# SparkFun_Clock_Generator_5PV49V60.net
KiCad netlist of a schematic drawn in EAGLE
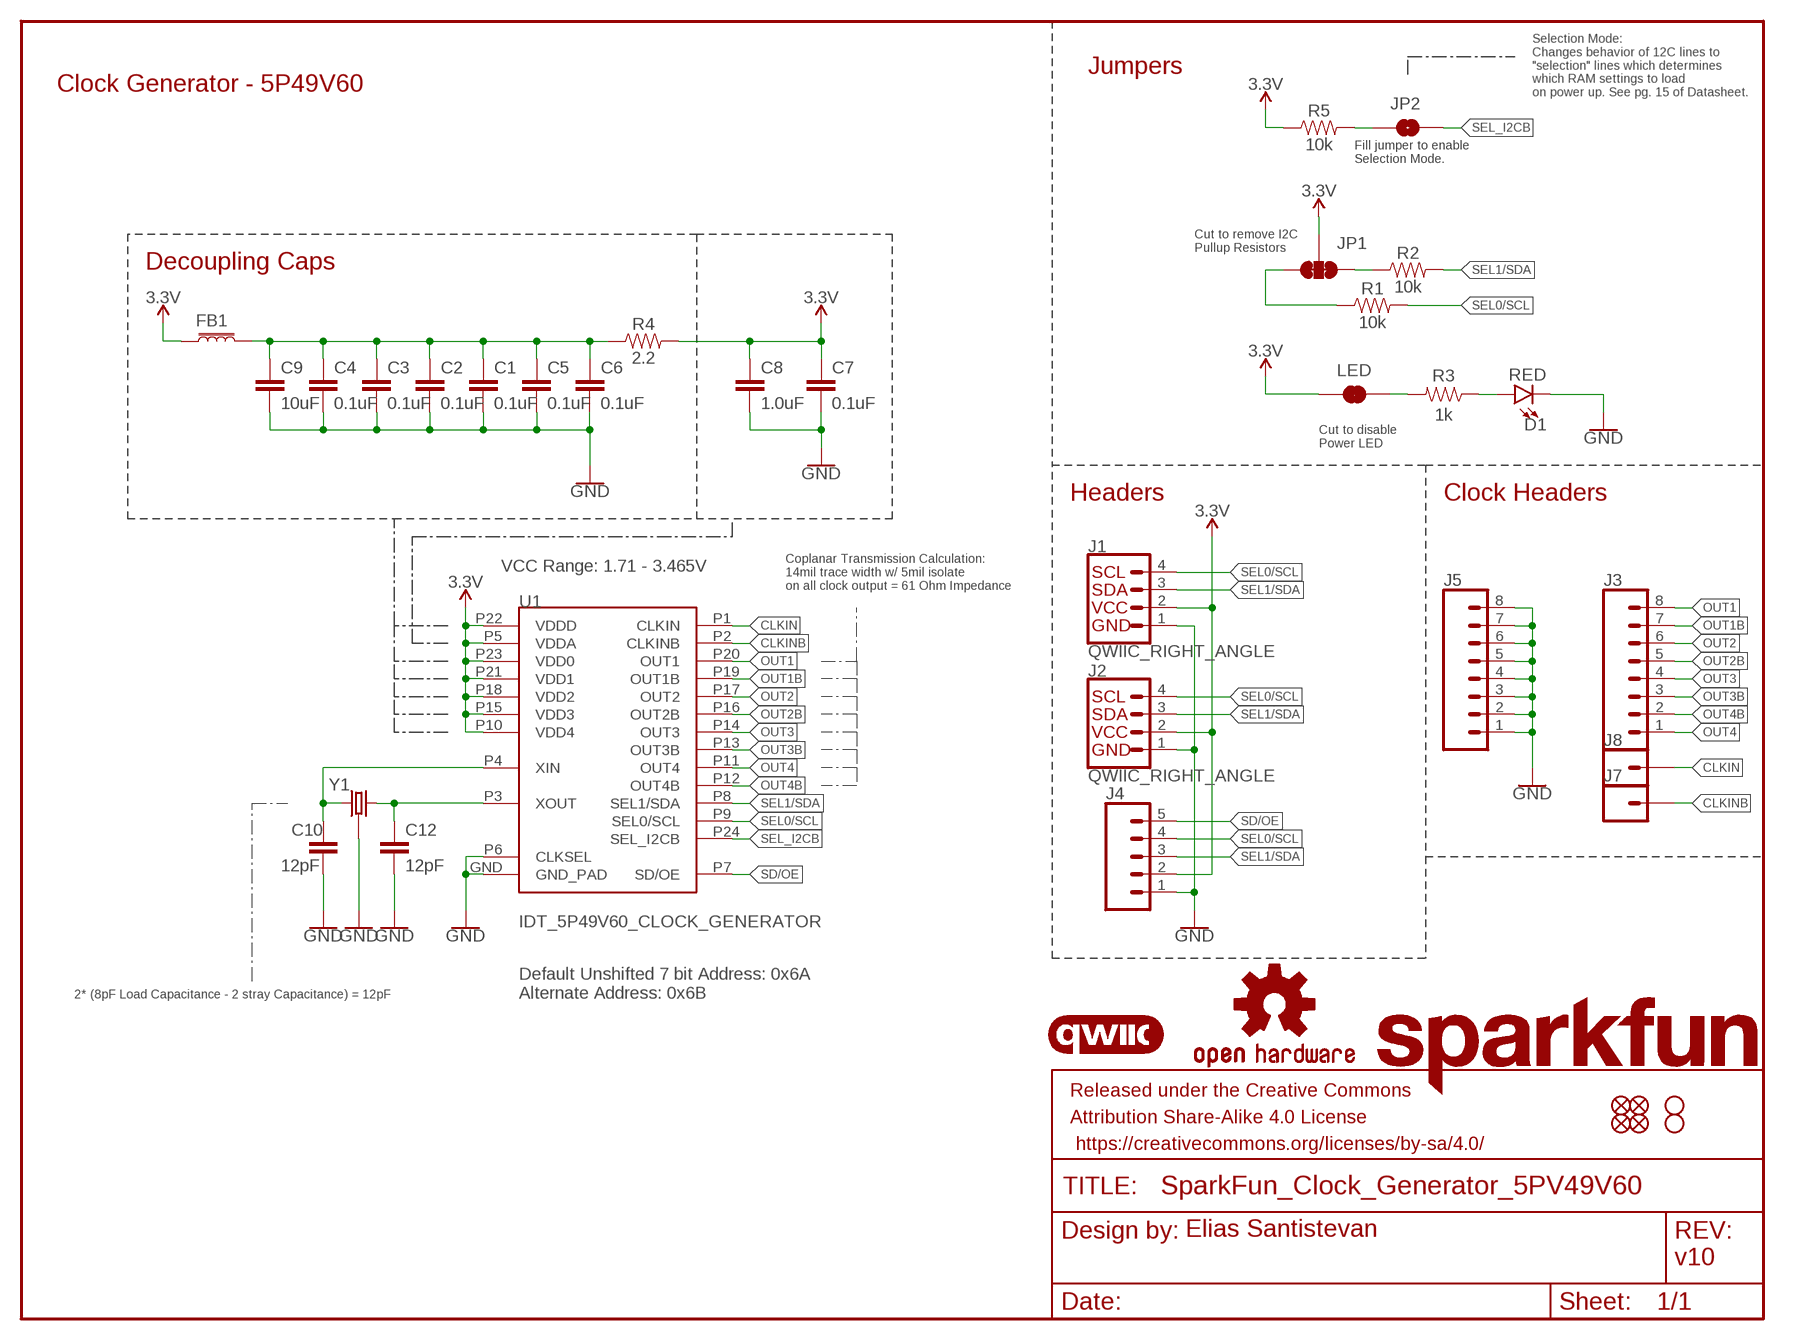
[diagram p0: schematic, sheet 1]

(export (version "E")
  (design (tool "Eeschema 10.0.6"))
  (components
    (comp (ref "C1")
      (value "0.1uF")
      (footprint "eagle-import:0402")
      (libsource (lib "eagle-import") (part "0.1UF-0402-16V-10%"))
    )
    (comp (ref "C2")
      (value "0.1uF")
      (footprint "eagle-import:0402")
      (libsource (lib "eagle-import") (part "0.1UF-0402-16V-10%"))
    )
    (comp (ref "C3")
      (value "0.1uF")
      (footprint "eagle-import:0402")
      (libsource (lib "eagle-import") (part "0.1UF-0402-16V-10%"))
    )
    (comp (ref "C4")
      (value "0.1uF")
      (footprint "eagle-import:0402")
      (libsource (lib "eagle-import") (part "0.1UF-0402-16V-10%"))
    )
    (comp (ref "C5")
      (value "0.1uF")
      (footprint "eagle-import:0402")
      (libsource (lib "eagle-import") (part "0.1UF-0402-16V-10%"))
    )
    (comp (ref "C6")
      (value "0.1uF")
      (footprint "eagle-import:0402")
      (libsource (lib "eagle-import") (part "0.1UF-0402-16V-10%"))
    )
    (comp (ref "C7")
      (value "0.1uF")
      (footprint "eagle-import:0402")
      (libsource (lib "eagle-import") (part "0.1UF-0402-16V-10%"))
    )
    (comp (ref "C8")
      (value "1.0uF")
      (footprint "eagle-import:0402")
      (libsource (lib "eagle-import") (part "1.0UF-0402-16V-10%"))
    )
    (comp (ref "C9")
      (value "10uF")
      (footprint "eagle-import:0603")
      (libsource (lib "eagle-import") (part "10UF-0603-6.3V-20%"))
    )
    (comp (ref "C10")
      (value "12pF")
      (footprint "eagle-import:0402")
      (libsource (lib "eagle-import") (part "12PF-0402-50V-5%"))
    )
    (comp (ref "C12")
      (value "12pF")
      (footprint "eagle-import:0402")
      (libsource (lib "eagle-import") (part "12PF-0402-50V-5%"))
    )
    (comp (ref "D1")
      (value "RED")
      (footprint "eagle-import:LED-0603")
      (libsource (lib "eagle-import") (part "LED-RED0603"))
    )
    (comp (ref "FB1")
      (value "FERRITE_BEAD-120_OHM-0402")
      (footprint "eagle-import:0402")
      (fields (field (name "MFG_PART") "BLM15HB121SN1D"))
      (libsource (lib "eagle-import") (part "FERRITE_BEAD-120_OHM-0402"))
    )
    (comp (ref "FD1")
      (value "FIDUCIALUFIDUCIAL")
      (footprint "eagle-import:FIDUCIAL-MICRO")
      (libsource (lib "eagle-import") (part "FIDUCIALUFIDUCIAL"))
    )
    (comp (ref "FD2")
      (value "FIDUCIALUFIDUCIAL")
      (footprint "eagle-import:FIDUCIAL-MICRO")
      (libsource (lib "eagle-import") (part "FIDUCIALUFIDUCIAL"))
    )
    (comp (ref "FD3")
      (value "FIDUCIALUFIDUCIAL")
      (footprint "eagle-import:FIDUCIAL-MICRO")
      (libsource (lib "eagle-import") (part "FIDUCIALUFIDUCIAL"))
    )
    (comp (ref "FD4")
      (value "FIDUCIALUFIDUCIAL")
      (footprint "eagle-import:FIDUCIAL-MICRO")
      (libsource (lib "eagle-import") (part "FIDUCIALUFIDUCIAL"))
    )
    (comp (ref "FRAME1")
      (value "FRAME-LETTER")
      (footprint "eagle-import:CREATIVE_COMMONS")
      (libsource (lib "eagle-import") (part "FRAME-LETTER"))
    )
    (comp (ref "H1")
      (value "STAND-OFFTIGHT")
      (footprint "eagle-import:STAND-OFF-TIGHT")
      (libsource (lib "eagle-import") (part "STAND-OFFTIGHT"))
    )
    (comp (ref "H2")
      (value "STAND-OFFTIGHT")
      (footprint "eagle-import:STAND-OFF-TIGHT")
      (libsource (lib "eagle-import") (part "STAND-OFFTIGHT"))
    )
    (comp (ref "J1")
      (value "QWIIC_RIGHT_ANGLE")
      (footprint "eagle-import:JST04_1MM_RA")
      (libsource (lib "eagle-import") (part "QWIIC_CONNECTORJS-1MM"))
    )
    (comp (ref "J2")
      (value "QWIIC_RIGHT_ANGLE")
      (footprint "eagle-import:JST04_1MM_RA")
      (libsource (lib "eagle-import") (part "QWIIC_CONNECTORJS-1MM"))
    )
    (comp (ref "J3")
      (value "CONN_08NO_SILK_FEMALE_PTH")
      (footprint "eagle-import:1X08_NO_SILK")
      (libsource (lib "eagle-import") (part "CONN_08NO_SILK_FEMALE_PTH"))
    )
    (comp (ref "J4")
      (value "CONN_05NO_SILK")
      (footprint "eagle-import:1X05_NO_SILK")
      (libsource (lib "eagle-import") (part "CONN_05NO_SILK"))
    )
    (comp (ref "J5")
      (value "CONN_08NO_SILK_FEMALE_PTH")
      (footprint "eagle-import:1X08_NO_SILK")
      (libsource (lib "eagle-import") (part "CONN_08NO_SILK_FEMALE_PTH"))
    )
    (comp (ref "J7")
      (value "CONN_01PTH_NO_SILK_SMALL")
      (footprint "eagle-import:1X01_SMALL")
      (libsource (lib "eagle-import") (part "CONN_01PTH_NO_SILK_SMALL"))
    )
    (comp (ref "J8")
      (value "CONN_01PTH_NO_SILK_SMALL")
      (footprint "eagle-import:1X01_SMALL")
      (libsource (lib "eagle-import") (part "CONN_01PTH_NO_SILK_SMALL"))
    )
    (comp (ref "JP1")
      (value "JUMPER-SMT_3_2-NC_TRACE_SILK")
      (footprint "eagle-import:SMT-JUMPER_3_2-NC_TRACE_SILK")
      (libsource (lib "eagle-import") (part "JUMPER-SMT_3_2-NC_TRACE_SILK"))
    )
    (comp (ref "JP2")
      (value "JUMPER-SMT_2_NO_SILK")
      (footprint "eagle-import:SMT-JUMPER_2_NO_SILK")
      (libsource (lib "eagle-import") (part "JUMPER-SMT_2_NO_SILK"))
    )
    (comp (ref "LED")
      (value "JUMPER-SMT_2_NC_TRACE_SILK")
      (footprint "eagle-import:SMT-JUMPER_2_NC_TRACE_SILK")
      (libsource (lib "eagle-import") (part "JUMPER-SMT_2_NC_TRACE_SILK"))
    )
    (comp (ref "LOGO1")
      (value "SFE_LOGO_NAME.1_INCH")
      (footprint "eagle-import:SFE_LOGO_NAME_.1")
      (libsource (lib "eagle-import") (part "SFE_LOGO_NAME.1_INCH"))
    )
    (comp (ref "LOGO2")
      (value "OSHW-LOGOS")
      (footprint "eagle-import:OSHW-LOGO-S")
      (libsource (lib "eagle-import") (part "OSHW-LOGOS"))
    )
    (comp (ref "LOGO3")
      (value "QWIIC_LOGO_4MM")
      (footprint "eagle-import:QWIIC_4MM")
      (libsource (lib "eagle-import") (part "QWIIC_LOGO_4MM"))
    )
    (comp (ref "R1")
      (value "10k")
      (footprint "eagle-import:0402")
      (libsource (lib "eagle-import") (part "10KOHM-0402-1/16W-1%"))
    )
    (comp (ref "R2")
      (value "10k")
      (footprint "eagle-import:0402")
      (libsource (lib "eagle-import") (part "10KOHM-0402-1/16W-1%"))
    )
    (comp (ref "R3")
      (value "1KOHM-0402-1/16W-1%")
      (footprint "eagle-import:0402")
      (libsource (lib "eagle-import") (part "1KOHM-0402-1/16W-1%"))
    )
    (comp (ref "R4")
      (value "2.2")
      (footprint "eagle-import:0603")
      (libsource (lib "eagle-import") (part "2.2OHM-0603-1/10W-5%"))
    )
    (comp (ref "R5")
      (value "10k")
      (footprint "eagle-import:0402")
      (libsource (lib "eagle-import") (part "10KOHM-0402-1/16W-1%"))
    )
    (comp (ref "U1")
      (value "IDT_5P49V60_CLOCK_GENERATOR")
      (footprint "eagle-import:VFQFPN-24")
      (libsource (lib "eagle-import") (part "IDT_5P49V60_CLOCK_GENERATOR"))
    )
    (comp (ref "Y1")
      (value "16MHz")
      (footprint "eagle-import:CRYSTAL-SMD-2X2.5MM")
      (libsource (lib "eagle-import") (part "CRYSTAL-16MHZ_SMALL"))
    )
  )
  (nets
    (net (code "1") (name "3.3V") (class "Default")
      (node (ref "C1") (pin "1") (pinfunction "1_1") (pintype "passive"))
      (node (ref "C2") (pin "1") (pinfunction "1_1") (pintype "passive"))
      (node (ref "C3") (pin "1") (pinfunction "1_1") (pintype "passive"))
      (node (ref "C4") (pin "1") (pinfunction "1_1") (pintype "passive"))
      (node (ref "C5") (pin "1") (pinfunction "1_1") (pintype "passive"))
      (node (ref "C6") (pin "1") (pinfunction "1_1") (pintype "passive"))
      (node (ref "C7") (pin "1") (pinfunction "1_1") (pintype "passive"))
      (node (ref "C8") (pin "1") (pinfunction "1_1") (pintype "passive"))
      (node (ref "C9") (pin "1") (pinfunction "1_1") (pintype "passive"))
      (node (ref "FB1") (pin "1") (pinfunction "1_1") (pintype "passive"))
      (node (ref "FB1") (pin "2") (pinfunction "2_2") (pintype "passive"))
      (node (ref "J1") (pin "2") (pinfunction "2_2") (pintype "power_in"))
      (node (ref "J2") (pin "2") (pinfunction "2_2") (pintype "power_in"))
      (node (ref "J4") (pin "2") (pinfunction "2_2") (pintype "passive"))
      (node (ref "JP1") (pin "2") (pinfunction "2_2") (pintype "passive"))
      (node (ref "LED") (pin "2") (pinfunction "2_2") (pintype "passive"))
      (node (ref "R4") (pin "1") (pinfunction "1_1") (pintype "passive"))
      (node (ref "R4") (pin "2") (pinfunction "2_2") (pintype "passive"))
      (node (ref "R5") (pin "1") (pinfunction "1_1") (pintype "passive"))
      (node (ref "U1") (pin "P10") (pinfunction "VDD4_P10") (pintype "power_in"))
      (node (ref "U1") (pin "P15") (pinfunction "VDD3_P15") (pintype "power_in"))
      (node (ref "U1") (pin "P18") (pinfunction "VDD2_P18") (pintype "power_in"))
      (node (ref "U1") (pin "P21") (pinfunction "VDD1_P21") (pintype "power_in"))
      (node (ref "U1") (pin "P22") (pinfunction "VDDD_P22") (pintype "power_in"))
      (node (ref "U1") (pin "P23") (pinfunction "VDD0_P23") (pintype "power_in"))
      (node (ref "U1") (pin "P5") (pinfunction "VDDA_P5") (pintype "power_in"))
    )
    (net (code "2") (name "CLKIN") (class "Default")
      (node (ref "J8") (pin "P$1") (pinfunction "1_P$1") (pintype "passive"))
      (node (ref "U1") (pin "P1") (pinfunction "CLKIN_P1") (pintype "bidirectional"))
    )
    (net (code "3") (name "CLKINB") (class "Default")
      (node (ref "J7") (pin "P$1") (pinfunction "1_P$1") (pintype "passive"))
      (node (ref "U1") (pin "P2") (pinfunction "CLKINB_P2") (pintype "power_in"))
    )
    (net (code "4") (name "GND") (class "Default")
      (node (ref "C1") (pin "2") (pinfunction "2_2") (pintype "passive"))
      (node (ref "C10") (pin "2") (pinfunction "2_2") (pintype "passive"))
      (node (ref "C12") (pin "2") (pinfunction "2_2") (pintype "passive"))
      (node (ref "C2") (pin "2") (pinfunction "2_2") (pintype "passive"))
      (node (ref "C3") (pin "2") (pinfunction "2_2") (pintype "passive"))
      (node (ref "C4") (pin "2") (pinfunction "2_2") (pintype "passive"))
      (node (ref "C5") (pin "2") (pinfunction "2_2") (pintype "passive"))
      (node (ref "C6") (pin "2") (pinfunction "2_2") (pintype "passive"))
      (node (ref "C7") (pin "2") (pinfunction "2_2") (pintype "passive"))
      (node (ref "C8") (pin "2") (pinfunction "2_2") (pintype "passive"))
      (node (ref "C9") (pin "2") (pinfunction "2_2") (pintype "passive"))
      (node (ref "D1") (pin "C") (pinfunction "C_C") (pintype "passive"))
      (node (ref "J1") (pin "1") (pinfunction "1_1") (pintype "power_in"))
      (node (ref "J2") (pin "1") (pinfunction "1_1") (pintype "power_in"))
      (node (ref "J4") (pin "1") (pinfunction "1_1") (pintype "passive"))
      (node (ref "J5") (pin "1") (pinfunction "1_1") (pintype "passive"))
      (node (ref "J5") (pin "2") (pinfunction "2_2") (pintype "passive"))
      (node (ref "J5") (pin "3") (pinfunction "3_3") (pintype "passive"))
      (node (ref "J5") (pin "4") (pinfunction "4_4") (pintype "passive"))
      (node (ref "J5") (pin "5") (pinfunction "5_5") (pintype "passive"))
      (node (ref "J5") (pin "6") (pinfunction "6_6") (pintype "passive"))
      (node (ref "J5") (pin "7") (pinfunction "7_7") (pintype "passive"))
      (node (ref "J5") (pin "8") (pinfunction "8_8") (pintype "passive"))
      (node (ref "U1") (pin "GND") (pinfunction "GND_PAD_GND") (pintype "power_in"))
      (node (ref "U1") (pin "P6") (pinfunction "CLKSEL_P6") (pintype "power_in"))
      (node (ref "Y1") (pin "P2") (pinfunction "GND_P2") (pintype "power_in"))
      (node (ref "Y1") (pin "P4") (pinfunction "GND_P4") (pintype "power_in"))
    )
    (net (code "5") (name "Net-(D1-PadA)") (class "Default")
      (node (ref "D1") (pin "A") (pinfunction "A_A") (pintype "passive"))
      (node (ref "R3") (pin "1") (pinfunction "1_1") (pintype "passive"))
    )
    (net (code "6") (name "Net-(JP1-Pad1)") (class "Default")
      (node (ref "JP1") (pin "1") (pinfunction "1_1") (pintype "passive"))
      (node (ref "R2") (pin "1") (pinfunction "1_1") (pintype "passive"))
    )
    (net (code "7") (name "Net-(JP1-Pad3)") (class "Default")
      (node (ref "JP1") (pin "3") (pinfunction "3_3") (pintype "passive"))
      (node (ref "R1") (pin "1") (pinfunction "1_1") (pintype "passive"))
    )
    (net (code "8") (name "Net-(JP2-Pad1)") (class "Default")
      (node (ref "JP2") (pin "1") (pinfunction "1_1") (pintype "passive"))
      (node (ref "R5") (pin "2") (pinfunction "2_2") (pintype "passive"))
    )
    (net (code "9") (name "Net-(LED-Pad1)") (class "Default")
      (node (ref "LED") (pin "1") (pinfunction "1_1") (pintype "passive"))
      (node (ref "R3") (pin "2") (pinfunction "2_2") (pintype "passive"))
    )
    (net (code "10") (name "Net-(U1-XIN)") (class "Default")
      (node (ref "C10") (pin "1") (pinfunction "1_1") (pintype "passive"))
      (node (ref "U1") (pin "P4") (pinfunction "XIN_P4") (pintype "bidirectional"))
      (node (ref "Y1") (pin "P3") (pinfunction "2_P3") (pintype "passive"))
    )
    (net (code "11") (name "Net-(U1-XOUT)") (class "Default")
      (node (ref "C12") (pin "1") (pinfunction "1_1") (pintype "passive"))
      (node (ref "U1") (pin "P3") (pinfunction "XOUT_P3") (pintype "bidirectional"))
      (node (ref "Y1") (pin "P1") (pinfunction "1_P1") (pintype "passive"))
    )
    (net (code "12") (name "OUT1") (class "Default")
      (node (ref "J3") (pin "8") (pinfunction "8_8") (pintype "passive"))
      (node (ref "U1") (pin "P20") (pinfunction "OUT1_P20") (pintype "bidirectional"))
    )
    (net (code "13") (name "OUT1B") (class "Default")
      (node (ref "J3") (pin "7") (pinfunction "7_7") (pintype "passive"))
      (node (ref "U1") (pin "P19") (pinfunction "OUT1B_P19") (pintype "bidirectional"))
    )
    (net (code "14") (name "OUT2") (class "Default")
      (node (ref "J3") (pin "6") (pinfunction "6_6") (pintype "passive"))
      (node (ref "U1") (pin "P17") (pinfunction "OUT2_P17") (pintype "bidirectional"))
    )
    (net (code "15") (name "OUT2B") (class "Default")
      (node (ref "J3") (pin "5") (pinfunction "5_5") (pintype "passive"))
      (node (ref "U1") (pin "P16") (pinfunction "OUT2B_P16") (pintype "bidirectional"))
    )
    (net (code "16") (name "OUT3") (class "Default")
      (node (ref "J3") (pin "4") (pinfunction "4_4") (pintype "passive"))
      (node (ref "U1") (pin "P14") (pinfunction "OUT3_P14") (pintype "bidirectional"))
    )
    (net (code "17") (name "OUT3B") (class "Default")
      (node (ref "J3") (pin "3") (pinfunction "3_3") (pintype "passive"))
      (node (ref "U1") (pin "P13") (pinfunction "OUT3B_P13") (pintype "bidirectional"))
    )
    (net (code "18") (name "OUT4") (class "Default")
      (node (ref "J3") (pin "1") (pinfunction "1_1") (pintype "passive"))
      (node (ref "U1") (pin "P11") (pinfunction "OUT4_P11") (pintype "bidirectional"))
    )
    (net (code "19") (name "OUT4B") (class "Default")
      (node (ref "J3") (pin "2") (pinfunction "2_2") (pintype "passive"))
      (node (ref "U1") (pin "P12") (pinfunction "OUT4B_P12") (pintype "bidirectional"))
    )
    (net (code "20") (name "SD{slash}OE") (class "Default")
      (node (ref "J4") (pin "5") (pinfunction "5_5") (pintype "passive"))
      (node (ref "U1") (pin "P7") (pinfunction "SD/OE_P7") (pintype "bidirectional"))
    )
    (net (code "21") (name "SEL0{slash}SCL") (class "Default")
      (node (ref "J1") (pin "4") (pinfunction "4_4") (pintype "passive"))
      (node (ref "J2") (pin "4") (pinfunction "4_4") (pintype "passive"))
      (node (ref "J4") (pin "4") (pinfunction "4_4") (pintype "passive"))
      (node (ref "R1") (pin "2") (pinfunction "2_2") (pintype "passive"))
      (node (ref "U1") (pin "P9") (pinfunction "SEL0/SCL_P9") (pintype "bidirectional"))
    )
    (net (code "22") (name "SEL1{slash}SDA") (class "Default")
      (node (ref "J1") (pin "3") (pinfunction "3_3") (pintype "passive"))
      (node (ref "J2") (pin "3") (pinfunction "3_3") (pintype "passive"))
      (node (ref "J4") (pin "3") (pinfunction "3_3") (pintype "passive"))
      (node (ref "R2") (pin "2") (pinfunction "2_2") (pintype "passive"))
      (node (ref "U1") (pin "P8") (pinfunction "SEL1/SDA_P8") (pintype "bidirectional"))
    )
    (net (code "23") (name "SEL_I2CB") (class "Default")
      (node (ref "JP2") (pin "2") (pinfunction "2_2") (pintype "passive"))
      (node (ref "U1") (pin "P24") (pinfunction "SEL_I2CB_P24") (pintype "power_in"))
    )
  )
)
